# POWER.net
KiCad netlist of a schematic drawn in Altium Designer
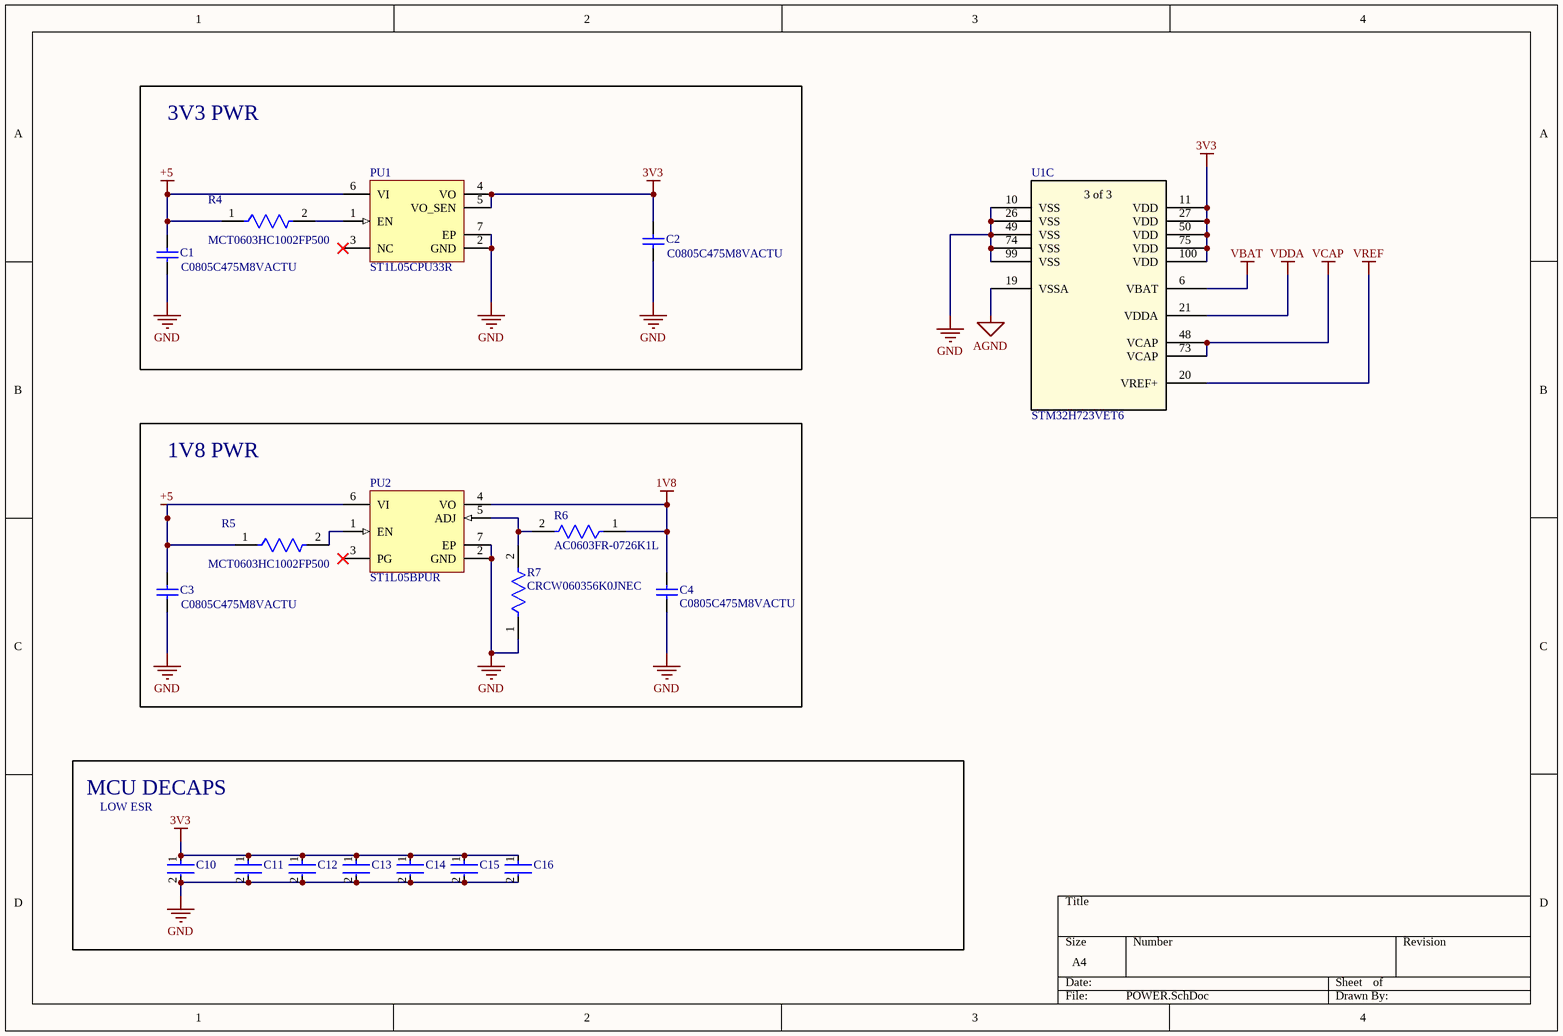
[diagram p0: POWER.SchDoc]

(export (version "E")
  (design (tool "Eeschema 10.0.6"))
  (components
    (comp (ref "C1")
      (value "C0805C475M8VACTU")
      (footprint "CAPC2013X145X50ML20T25")
      (fields (field (name "MANUFACTURER") "Kemet"))
      (libsource (lib "Altium Content Vault") (part "CAP"))
    )
    (comp (ref "C2")
      (value "C0805C475M8VACTU")
      (footprint "CAPC2013X145X50ML20T25")
      (fields (field (name "MANUFACTURER") "Kemet"))
      (libsource (lib "Altium Content Vault") (part "CAP"))
    )
    (comp (ref "C3")
      (value "C0805C475M8VACTU")
      (footprint "CAPC2013X145X50ML20T25")
      (fields (field (name "MANUFACTURER") "Kemet"))
      (libsource (lib "Altium Content Vault") (part "CAP"))
    )
    (comp (ref "C4")
      (value "C0805C475M8VACTU")
      (footprint "CAPC2013X145X50ML20T25")
      (fields (field (name "MANUFACTURER") "Kemet"))
      (libsource (lib "Altium Content Vault") (part "CAP"))
    )
    (comp (ref "C10")
      (value "C0603X6S1C104K030BC")
      (footprint "FP-C0603-030-0_03-IPC_B")
      (description "Multilayer Ceramic Capacitors 100nF ±10% 16V X6S SMD 0201")
      (fields (field (name "TOLERANCE") "10%"))
      (libsource (lib "Altium Content Vault") (part "02cd4be3c70576c341d710602a673aa"))
    )
    (comp (ref "C11")
      (value "C0603X6S1C104K030BC")
      (footprint "FP-C0603-030-0_03-IPC_B")
      (description "Multilayer Ceramic Capacitors 100nF ±10% 16V X6S SMD 0201")
      (fields (field (name "TOLERANCE") "10%"))
      (libsource (lib "Altium Content Vault") (part "02cd4be3c70576c341d710602a673aa"))
    )
    (comp (ref "C12")
      (value "C0603X6S1C104K030BC")
      (footprint "FP-C0603-030-0_03-IPC_B")
      (description "Multilayer Ceramic Capacitors 100nF ±10% 16V X6S SMD 0201")
      (fields (field (name "TOLERANCE") "10%"))
      (libsource (lib "Altium Content Vault") (part "02cd4be3c70576c341d710602a673aa"))
    )
    (comp (ref "C13")
      (value "C0603X6S1C104K030BC")
      (footprint "FP-C0603-030-0_03-IPC_B")
      (description "Multilayer Ceramic Capacitors 100nF ±10% 16V X6S SMD 0201")
      (fields (field (name "TOLERANCE") "10%"))
      (libsource (lib "Altium Content Vault") (part "02cd4be3c70576c341d710602a673aa"))
    )
    (comp (ref "C14")
      (value "C0603X6S1C104K030BC")
      (footprint "FP-C0603-030-0_03-IPC_B")
      (description "Multilayer Ceramic Capacitors 100nF ±10% 16V X6S SMD 0201")
      (fields (field (name "TOLERANCE") "10%"))
      (libsource (lib "Altium Content Vault") (part "02cd4be3c70576c341d710602a673aa"))
    )
    (comp (ref "C15")
      (value "C0603X6S1C104K030BC")
      (footprint "FP-C0603-030-0_03-IPC_B")
      (description "Multilayer Ceramic Capacitors 100nF ±10% 16V X6S SMD 0201")
      (fields (field (name "TOLERANCE") "10%"))
      (libsource (lib "Altium Content Vault") (part "02cd4be3c70576c341d710602a673aa"))
    )
    (comp (ref "C16")
      (value "C0603X6S1C104K030BC")
      (footprint "FP-C0603-030-0_03-IPC_B")
      (description "Multilayer Ceramic Capacitors 100nF ±10% 16V X6S SMD 0201")
      (fields (field (name "TOLERANCE") "10%"))
      (libsource (lib "Altium Content Vault") (part "02cd4be3c70576c341d710602a673aa"))
    )
    (comp (ref "PU1")
      (value "ST1L05CPU33R")
      (footprint "DFN6D_N")
      (description "Very Low Quiescent BiCMOS Voltage Regulator, 3.3V, 6-Pin VFDFPN, Tape and Reel")
      (libsource (lib "Altium Content Vault") (part "PM-REG-ST1L05C-SQ7"))
    )
    (comp (ref "PU2")
      (value "ST1L05BPUR")
      (footprint "DFN6D_M")
      (description "Very Low Quiescent BiCMOS Voltage Regulator, Adjustable Vo, 6-Pin VFDFPN, Tape and Reel")
      (libsource (lib "Altium Content Vault") (part "PM-REG-ST1L05B-SQ7A"))
    )
    (comp (ref "R4")
      (value "MCT0603HC1002FP500")
      (footprint "FP-MCT0603-IPC_B")
      (description "RES SMD 100 OHM 1% 1/8W 0603")
      (libsource (lib "Altium Content Vault") (part "1029c3af85768c4190bb7ad29bc67b5"))
    )
    (comp (ref "R5")
      (value "MCT0603HC1002FP500")
      (footprint "FP-MCT0603-IPC_B")
      (description "RES SMD 100 OHM 1% 1/8W 0603")
      (libsource (lib "Altium Content Vault") (part "1029c3af85768c4190bb7ad29bc67b5"))
    )
    (comp (ref "R6")
      (value "AC0603FR-0726K1L")
      (footprint "FP-AC0603-MFG")
      (description "RES 26.1KΩ 1.00% 0.1W 0603")
      (fields (field (name "TOLERANCE") "1%"))
      (libsource (lib "Altium Content Vault") (part "1029c3af85768c4190bb7ad29bc67b5"))
    )
    (comp (ref "R7")
      (value "CRCW060356K0JNEC")
      (footprint "FP-CRCW0603-e3-IPC_A")
      (description "RES Thick Film, 56kΩ, 5%, 0.1W, 200ppm/°C, 0603")
      (fields (field (name "TOLERANCE") "5%"))
      (libsource (lib "Altium Content Vault") (part "1029c3af85768c4190bb7ad29bc67b5"))
    )
    (comp (ref "U1")
      (value "STM32H723VET6")
      (footprint "LQFP100_STM")
      (fields (field (name "COPYRIGHT") "Copyright (C) 2025 Ultra Librarian. All rights reserved."))
      (libsource (lib "STM32H723VET6") (part "STM32H723VET6"))
    )
  )
  (nets
    (net (code "1") (name "+5") (class "Default")
      (node (ref "C1") (pin "2") (pinfunction "2_2") (pintype "passive"))
      (node (ref "C3") (pin "2") (pinfunction "2_2") (pintype "passive"))
      (node (ref "PU1") (pin "6") (pinfunction "VI_6") (pintype "power_in"))
      (node (ref "PU2") (pin "6") (pinfunction "VI_6") (pintype "power_in"))
      (node (ref "R4") (pin "1") (pinfunction "1_1") (pintype "passive"))
      (node (ref "R5") (pin "1") (pinfunction "1_1") (pintype "passive"))
    )
    (net (code "2") (name "1V8") (class "Default")
      (node (ref "C4") (pin "2") (pinfunction "2_2") (pintype "passive"))
      (node (ref "PU2") (pin "4") (pinfunction "VO_4") (pintype "power_in"))
      (node (ref "R6") (pin "1") (pinfunction "1_1") (pintype "passive"))
    )
    (net (code "3") (name "3V3") (class "Default")
      (node (ref "C10") (pin "1") (pinfunction "1_1") (pintype "passive"))
      (node (ref "C11") (pin "1") (pinfunction "1_1") (pintype "passive"))
      (node (ref "C12") (pin "1") (pinfunction "1_1") (pintype "passive"))
      (node (ref "C13") (pin "1") (pinfunction "1_1") (pintype "passive"))
      (node (ref "C14") (pin "1") (pinfunction "1_1") (pintype "passive"))
      (node (ref "C15") (pin "1") (pinfunction "1_1") (pintype "passive"))
      (node (ref "C16") (pin "1") (pinfunction "1_1") (pintype "passive"))
      (node (ref "C2") (pin "2") (pinfunction "2_2") (pintype "passive"))
      (node (ref "PU1") (pin "4") (pinfunction "VO_4") (pintype "power_in"))
      (node (ref "PU1") (pin "5") (pinfunction "VO_SEN_5") (pintype "passive"))
      (node (ref "U1") (pin "100") (pinfunction "VDD_100") (pintype "power_in"))
      (node (ref "U1") (pin "11") (pinfunction "VDD_11") (pintype "power_in"))
      (node (ref "U1") (pin "27") (pinfunction "VDD_27") (pintype "power_in"))
      (node (ref "U1") (pin "50") (pinfunction "VDD_50") (pintype "power_in"))
      (node (ref "U1") (pin "75") (pinfunction "VDD_75") (pintype "power_in"))
    )
    (net (code "4") (name "AGND") (class "Default")
      (node (ref "U1") (pin "19") (pinfunction "VSSA_19") (pintype "power_in"))
    )
    (net (code "5") (name "GND") (class "Default")
      (node (ref "C1") (pin "1") (pinfunction "1_1") (pintype "passive"))
      (node (ref "C10") (pin "2") (pinfunction "2_2") (pintype "passive"))
      (node (ref "C11") (pin "2") (pinfunction "2_2") (pintype "passive"))
      (node (ref "C12") (pin "2") (pinfunction "2_2") (pintype "passive"))
      (node (ref "C13") (pin "2") (pinfunction "2_2") (pintype "passive"))
      (node (ref "C14") (pin "2") (pinfunction "2_2") (pintype "passive"))
      (node (ref "C15") (pin "2") (pinfunction "2_2") (pintype "passive"))
      (node (ref "C16") (pin "2") (pinfunction "2_2") (pintype "passive"))
      (node (ref "C2") (pin "1") (pinfunction "1_1") (pintype "passive"))
      (node (ref "C3") (pin "1") (pinfunction "1_1") (pintype "passive"))
      (node (ref "C4") (pin "1") (pinfunction "1_1") (pintype "passive"))
      (node (ref "PU1") (pin "2") (pinfunction "GND_2") (pintype "power_in"))
      (node (ref "PU1") (pin "7") (pinfunction "EP_7") (pintype "power_in"))
      (node (ref "PU2") (pin "2") (pinfunction "GND_2") (pintype "power_in"))
      (node (ref "PU2") (pin "7") (pinfunction "EP_7") (pintype "power_in"))
      (node (ref "R7") (pin "1") (pinfunction "1_1") (pintype "passive"))
      (node (ref "U1") (pin "10") (pinfunction "VSS_10") (pintype "power_in"))
      (node (ref "U1") (pin "26") (pinfunction "VSS_26") (pintype "power_in"))
      (node (ref "U1") (pin "49") (pinfunction "VSS_49") (pintype "power_in"))
      (node (ref "U1") (pin "74") (pinfunction "VSS_74") (pintype "power_in"))
      (node (ref "U1") (pin "99") (pinfunction "VSS_99") (pintype "power_in"))
    )
    (net (code "6") (name "Net-(PU1-EN)") (class "Default")
      (node (ref "PU1") (pin "1") (pinfunction "EN_1") (pintype "input"))
      (node (ref "R4") (pin "2") (pinfunction "2_2") (pintype "passive"))
    )
    (net (code "7") (name "Net-(PU2-ADJ)") (class "Default")
      (node (ref "PU2") (pin "5") (pinfunction "ADJ_5") (pintype "input"))
      (node (ref "R6") (pin "2") (pinfunction "2_2") (pintype "passive"))
      (node (ref "R7") (pin "2") (pinfunction "2_2") (pintype "passive"))
    )
    (net (code "8") (name "Net-(PU2-EN)") (class "Default")
      (node (ref "PU2") (pin "1") (pinfunction "EN_1") (pintype "input"))
      (node (ref "R5") (pin "2") (pinfunction "2_2") (pintype "passive"))
    )
    (net (code "9") (name "VBAT") (class "Default")
      (node (ref "U1") (pin "6") (pinfunction "VBAT_6") (pintype "power_in"))
    )
    (net (code "10") (name "VCAP") (class "Default")
      (node (ref "U1") (pin "48") (pinfunction "VCAP_48") (pintype "power_in"))
      (node (ref "U1") (pin "73") (pinfunction "VCAP_73") (pintype "power_in"))
    )
    (net (code "11") (name "VDDA") (class "Default")
      (node (ref "U1") (pin "21") (pinfunction "VDDA_21") (pintype "power_in"))
    )
    (net (code "12") (name "VREF") (class "Default")
      (node (ref "U1") (pin "20") (pinfunction "VREF+_20") (pintype "power_in"))
    )
    (net (code "13") (name "unconnected-(PU1-NC-Pad3)") (class "Default")
      (node (ref "PU1") (pin "3") (pinfunction "NC_3") (pintype "passive+no_connect"))
    )
    (net (code "14") (name "unconnected-(PU2-PG-Pad3)") (class "Default")
      (node (ref "PU2") (pin "3") (pinfunction "PG_3") (pintype "open_collector+no_connect"))
    )
  )
)
